# masterPuck.net
KiCad netlist of a schematic drawn in EAGLE
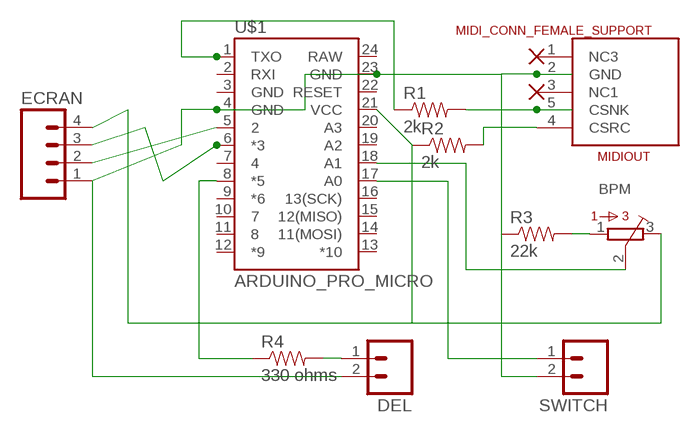
[diagram p0: schematic, sheet 1]

(export (version "E")
  (design (tool "Eeschema 10.0.6"))
  (components
    (comp (ref "BPM")
      (value "3386-P")
      (footprint "eagle-import:3386P")
      (libsource (lib "eagle-import") (part "3386-P"))
    )
    (comp (ref "DEL")
      (value "M02LOCK")
      (footprint "eagle-import:1X02_LOCK")
      (libsource (lib "eagle-import") (part "M02LOCK"))
    )
    (comp (ref "ECRAN")
      (value "M04PTH")
      (footprint "eagle-import:1X04")
      (libsource (lib "eagle-import") (part "M04PTH"))
    )
    (comp (ref "MIDIOUT")
      (value "MIDI_CONN_FEMALE_SUPPORT")
      (footprint "eagle-import:DIN_5_FEMALE_SUPPORT")
      (libsource (lib "eagle-import") (part "MIDI_CONN_FEMALE_SUPPORT"))
    )
    (comp (ref "R1")
      (value "2k")
      (footprint "eagle-import:1206")
      (libsource (lib "eagle-import") (part "RESISTOR1206"))
    )
    (comp (ref "R2")
      (value "2k")
      (footprint "eagle-import:1206")
      (libsource (lib "eagle-import") (part "RESISTOR1206"))
    )
    (comp (ref "R3")
      (value "22k")
      (footprint "eagle-import:1206")
      (libsource (lib "eagle-import") (part "RESISTOR1206"))
    )
    (comp (ref "R4")
      (value "330 ohms")
      (footprint "eagle-import:1206")
      (libsource (lib "eagle-import") (part "RESISTOR1206"))
    )
    (comp (ref "SWITCH")
      (value "M02LOCK")
      (footprint "eagle-import:1X02_LOCK")
      (libsource (lib "eagle-import") (part "M02LOCK"))
    )
    (comp (ref "U$1")
      (value "ARDUINO_PRO_MICRO")
      (footprint "eagle-import:ARDUINO_PRO_MICRO")
      (libsource (lib "eagle-import") (part "ARDUINO_PRO_MICRO"))
    )
  )
  (nets
    (net (code "1") (name "Net-(BPM-Pad1)") (class "Default")
      (node (ref "BPM") (pin "1") (pinfunction "1_1") (pintype "passive"))
      (node (ref "R3") (pin "2") (pinfunction "2_2") (pintype "passive"))
    )
    (net (code "2") (name "Net-(DEL-Pad1)") (class "Default")
      (node (ref "DEL") (pin "1") (pinfunction "1_1") (pintype "passive"))
      (node (ref "R4") (pin "2") (pinfunction "2_2") (pintype "passive"))
    )
    (net (code "3") (name "Net-(MIDIOUT-CSNK)") (class "Default")
      (node (ref "MIDIOUT") (pin "5") (pinfunction "CSNK_5") (pintype "bidirectional"))
      (node (ref "R1") (pin "2") (pinfunction "2_2") (pintype "passive"))
    )
    (net (code "4") (name "Net-(MIDIOUT-CSRC)") (class "Default")
      (node (ref "MIDIOUT") (pin "4") (pinfunction "CSRC_4") (pintype "bidirectional"))
      (node (ref "R2") (pin "2") (pinfunction "2_2") (pintype "passive"))
    )
    (net (code "5") (name "Net-(MIDIOUT-GND)") (class "Default")
      (node (ref "DEL") (pin "2") (pinfunction "2_2") (pintype "passive"))
      (node (ref "ECRAN") (pin "1") (pinfunction "1_1") (pintype "passive"))
      (node (ref "MIDIOUT") (pin "2") (pinfunction "GND_2") (pintype "bidirectional"))
      (node (ref "R3") (pin "1") (pinfunction "1_1") (pintype "passive"))
      (node (ref "SWITCH") (pin "2") (pinfunction "2_2") (pintype "passive"))
      (node (ref "U$1") (pin "23") (pinfunction "GND_23") (pintype "bidirectional"))
      (node (ref "U$1") (pin "4") (pinfunction "GND_4") (pintype "bidirectional"))
    )
    (net (code "6") (name "Net-(U$1-*3)") (class "Default")
      (node (ref "ECRAN") (pin "3") (pinfunction "3_3") (pintype "passive"))
      (node (ref "U$1") (pin "6") (pinfunction "*3_6") (pintype "bidirectional"))
    )
    (net (code "7") (name "Net-(U$1-*5)") (class "Default")
      (node (ref "R4") (pin "1") (pinfunction "1_1") (pintype "passive"))
      (node (ref "U$1") (pin "8") (pinfunction "*5_8") (pintype "bidirectional"))
    )
    (net (code "8") (name "Net-(U$1-2)") (class "Default")
      (node (ref "ECRAN") (pin "2") (pinfunction "2_2") (pintype "passive"))
      (node (ref "U$1") (pin "5") (pinfunction "2_5") (pintype "bidirectional"))
    )
    (net (code "9") (name "Net-(U$1-A0)") (class "Default")
      (node (ref "SWITCH") (pin "1") (pinfunction "1_1") (pintype "passive"))
      (node (ref "U$1") (pin "17") (pinfunction "A0_17") (pintype "bidirectional"))
    )
    (net (code "10") (name "Net-(U$1-A1)") (class "Default")
      (node (ref "BPM") (pin "2") (pinfunction "2_2") (pintype "passive"))
      (node (ref "U$1") (pin "18") (pinfunction "A1_18") (pintype "bidirectional"))
    )
    (net (code "11") (name "Net-(U$1-TXO)") (class "Default")
      (node (ref "R1") (pin "1") (pinfunction "1_1") (pintype "passive"))
      (node (ref "U$1") (pin "1") (pinfunction "TXO_1") (pintype "bidirectional"))
    )
    (net (code "12") (name "Net-(U$1-VCC)") (class "Default")
      (node (ref "BPM") (pin "3") (pinfunction "3_3") (pintype "passive"))
      (node (ref "ECRAN") (pin "4") (pinfunction "4_4") (pintype "passive"))
      (node (ref "R2") (pin "1") (pinfunction "1_1") (pintype "passive"))
      (node (ref "U$1") (pin "21") (pinfunction "VCC_21") (pintype "bidirectional"))
    )
    (net (code "13") (name "unconnected-(MIDIOUT-NC1-Pad3)") (class "Default")
      (node (ref "MIDIOUT") (pin "3") (pinfunction "NC1_3") (pintype "bidirectional"))
    )
    (net (code "14") (name "unconnected-(MIDIOUT-NC3-Pad1)") (class "Default")
      (node (ref "MIDIOUT") (pin "1") (pinfunction "NC3_1") (pintype "bidirectional"))
    )
    (net (code "15") (name "unconnected-(U$1-*6-Pad9)") (class "Default")
      (node (ref "U$1") (pin "9") (pinfunction "*6_9") (pintype "bidirectional"))
    )
    (net (code "16") (name "unconnected-(U$1-*9-Pad12)") (class "Default")
      (node (ref "U$1") (pin "12") (pinfunction "*9_12") (pintype "bidirectional"))
    )
    (net (code "17") (name "unconnected-(U$1-*10-Pad13)") (class "Default")
      (node (ref "U$1") (pin "13") (pinfunction "*10_13") (pintype "bidirectional"))
    )
    (net (code "18") (name "unconnected-(U$1-4-Pad7)") (class "Default")
      (node (ref "U$1") (pin "7") (pinfunction "4_7") (pintype "bidirectional"))
    )
    (net (code "19") (name "unconnected-(U$1-7-Pad10)") (class "Default")
      (node (ref "U$1") (pin "10") (pinfunction "7_10") (pintype "bidirectional"))
    )
    (net (code "20") (name "unconnected-(U$1-8-Pad11)") (class "Default")
      (node (ref "U$1") (pin "11") (pinfunction "8_11") (pintype "bidirectional"))
    )
    (net (code "21") (name "unconnected-(U$1-11(MOSI)-Pad14)") (class "Default")
      (node (ref "U$1") (pin "14") (pinfunction "11(MOSI)_14") (pintype "bidirectional"))
    )
    (net (code "22") (name "unconnected-(U$1-12(MISO)-Pad15)") (class "Default")
      (node (ref "U$1") (pin "15") (pinfunction "12(MISO)_15") (pintype "bidirectional"))
    )
    (net (code "23") (name "unconnected-(U$1-13(SCK)-Pad16)") (class "Default")
      (node (ref "U$1") (pin "16") (pinfunction "13(SCK)_16") (pintype "bidirectional"))
    )
    (net (code "24") (name "unconnected-(U$1-A2-Pad19)") (class "Default")
      (node (ref "U$1") (pin "19") (pinfunction "A2_19") (pintype "bidirectional"))
    )
    (net (code "25") (name "unconnected-(U$1-A3-Pad20)") (class "Default")
      (node (ref "U$1") (pin "20") (pinfunction "A3_20") (pintype "bidirectional"))
    )
    (net (code "26") (name "unconnected-(U$1-GND-Pad3)") (class "Default")
      (node (ref "U$1") (pin "3") (pinfunction "GND_3") (pintype "bidirectional"))
    )
    (net (code "27") (name "unconnected-(U$1-RAW-Pad24)") (class "Default")
      (node (ref "U$1") (pin "24") (pinfunction "RAW_24") (pintype "bidirectional"))
    )
    (net (code "28") (name "unconnected-(U$1-RESET-Pad22)") (class "Default")
      (node (ref "U$1") (pin "22") (pinfunction "RESET_22") (pintype "bidirectional"))
    )
    (net (code "29") (name "unconnected-(U$1-RXI-Pad2)") (class "Default")
      (node (ref "U$1") (pin "2") (pinfunction "RXI_2") (pintype "bidirectional"))
    )
  )
)
